# I2C_CAN.net
KiCad netlist of a schematic drawn in EAGLE
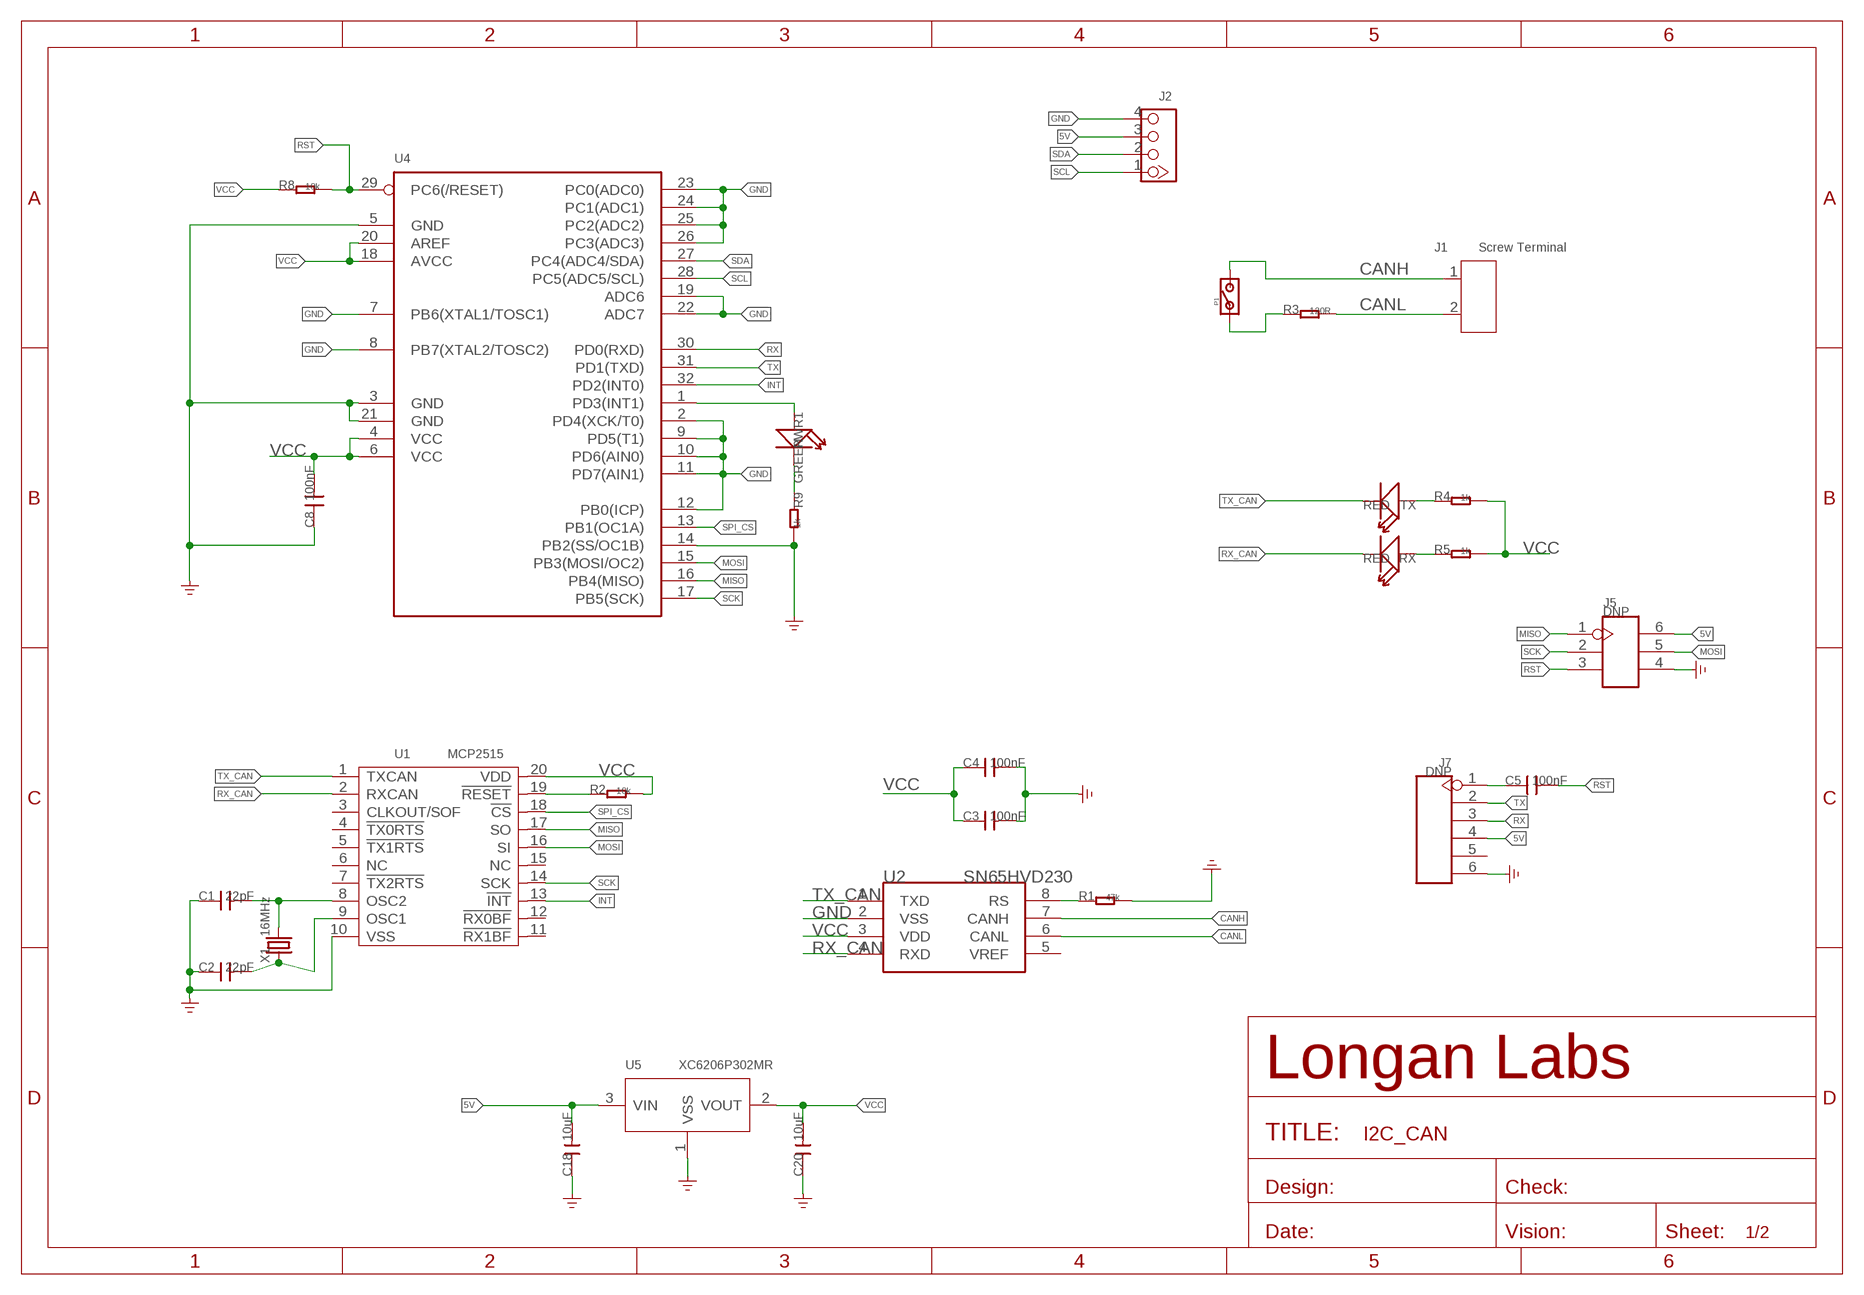
[diagram p0: schematic, sheet 1]

(export (version "E")
  (design (tool "Eeschema 10.0.6"))
  (components
    (comp (ref "C1")
      (value "22pF")
      (footprint "eagle-import:0603")
      (libsource (lib "eagle-import") (part "C-0603"))
    )
    (comp (ref "C2")
      (value "22pF")
      (footprint "eagle-import:0603")
      (libsource (lib "eagle-import") (part "C-0603"))
    )
    (comp (ref "C3")
      (value "100nF")
      (footprint "eagle-import:0603")
      (libsource (lib "eagle-import") (part "C-0603"))
    )
    (comp (ref "C4")
      (value "100nF")
      (footprint "eagle-import:0603")
      (libsource (lib "eagle-import") (part "C-0603"))
    )
    (comp (ref "C5")
      (value "100nF")
      (footprint "eagle-import:0603")
      (libsource (lib "eagle-import") (part "C-0603"))
    )
    (comp (ref "C8")
      (value "100nF")
      (footprint "eagle-import:0603")
      (libsource (lib "eagle-import") (part "C-0603"))
    )
    (comp (ref "C18")
      (value "10uF")
      (footprint "eagle-import:C0603")
      (libsource (lib "eagle-import") (part "CAP-0603"))
    )
    (comp (ref "C20")
      (value "10uF")
      (footprint "eagle-import:C0603")
      (libsource (lib "eagle-import") (part "CAP-0603"))
    )
    (comp (ref "J1")
      (value "Screw Terminal")
      (footprint "eagle-import:2P-3.5")
      (libsource (lib "eagle-import") (part "SCREW-TERMINAL-2P'3.5'"))
    )
    (comp (ref "J2")
      (value "320110033")
      (footprint "eagle-import:HW4-2.0")
      (libsource (lib "eagle-import") (part "GROVE-CONNECTOR-DIP-2.0"))
    )
    (comp (ref "J5")
      (value "DNP")
      (footprint "eagle-import:H2X3-SMD-2.0(1.143)")
      (libsource (lib "eagle-import") (part "HEADER-2X3P-2.0-1.143"))
    )
    (comp (ref "J7")
      (value "DNP")
      (footprint "eagle-import:H6-2.54")
      (libsource (lib "eagle-import") (part "HEADER-6P-55/35MIL"))
    )
    (comp (ref "P1")
      (value "PAD-JUMPER-2P")
      (footprint "eagle-import:2P-SMD-1.78X1.27")
      (libsource (lib "eagle-import") (part "PAD-JUMPER-2P"))
    )
    (comp (ref "PWR1")
      (value "GREEN")
      (footprint "eagle-import:LED-0603")
      (libsource (lib "eagle-import") (part "LED'0603'"))
    )
    (comp (ref "R1")
      (value "47k")
      (footprint "eagle-import:0603")
      (libsource (lib "eagle-import") (part "R-0603"))
    )
    (comp (ref "R2")
      (value "10k")
      (footprint "eagle-import:0603")
      (libsource (lib "eagle-import") (part "R-0603"))
    )
    (comp (ref "R3")
      (value "120R")
      (footprint "eagle-import:0603")
      (libsource (lib "eagle-import") (part "R-0603"))
    )
    (comp (ref "R4")
      (value "1k")
      (footprint "eagle-import:0603")
      (libsource (lib "eagle-import") (part "R-0603"))
    )
    (comp (ref "R5")
      (value "1k")
      (footprint "eagle-import:0603")
      (libsource (lib "eagle-import") (part "R-0603"))
    )
    (comp (ref "R8")
      (value "10k")
      (footprint "eagle-import:0603")
      (libsource (lib "eagle-import") (part "R-0603"))
    )
    (comp (ref "R9")
      (value "1k")
      (footprint "eagle-import:0603")
      (libsource (lib "eagle-import") (part "R-0603"))
    )
    (comp (ref "RX")
      (value "RED")
      (footprint "eagle-import:LED-0603")
      (libsource (lib "eagle-import") (part "LED'0603'"))
    )
    (comp (ref "TX")
      (value "RED")
      (footprint "eagle-import:LED-0603")
      (libsource (lib "eagle-import") (part "LED'0603'"))
    )
    (comp (ref "U1")
      (value "MCP2515")
      (footprint "eagle-import:TSSOP20-0.65-6.5X4.4MM")
      (libsource (lib "eagle-import") (part "MCP2515'ST'"))
    )
    (comp (ref "U2")
      (value "SN65HVD230")
      (footprint "eagle-import:SOIC8-6.0")
      (libsource (lib "eagle-import") (part "MCP2551-SOIC8"))
    )
    (comp (ref "U4")
      (value "MCU-ATMEGA8/168/328'AU'")
      (footprint "eagle-import:TQFP32-0.8-7X7MM")
      (libsource (lib "eagle-import") (part "MCU-ATMEGA8/168/328'AU'"))
    )
    (comp (ref "U5")
      (value "XC6206P302MR")
      (footprint "eagle-import:SOT-23")
      (libsource (lib "eagle-import") (part "PMIC-XC6206PMR"))
    )
    (comp (ref "X1")
      (value "16MHz")
      (footprint "eagle-import:HC49US")
      (libsource (lib "eagle-import") (part "CRYSTAL-2P'HC49US'"))
    )
  )
  (nets
    (net (code "1") (name "5V") (class "Default")
      (node (ref "C18") (pin "2") (pinfunction "2_2") (pintype "passive"))
      (node (ref "J2") (pin "3") (pinfunction "3_3") (pintype "bidirectional"))
      (node (ref "J5") (pin "6") (pinfunction "6_6") (pintype "bidirectional"))
      (node (ref "J7") (pin "4") (pinfunction "4_4") (pintype "bidirectional"))
      (node (ref "U5") (pin "3") (pinfunction "VIN_3") (pintype "bidirectional"))
    )
    (net (code "2") (name "CANH") (class "Default")
      (node (ref "J1") (pin "1") (pinfunction "1_1") (pintype "bidirectional"))
      (node (ref "P1") (pin "2") (pinfunction "2_2") (pintype "bidirectional"))
      (node (ref "U2") (pin "7") (pinfunction "CANH_7") (pintype "bidirectional"))
    )
    (net (code "3") (name "CANL") (class "Default")
      (node (ref "J1") (pin "2") (pinfunction "2_2") (pintype "bidirectional"))
      (node (ref "R3") (pin "2") (pinfunction "2_2") (pintype "passive"))
      (node (ref "U2") (pin "6") (pinfunction "CANL_6") (pintype "bidirectional"))
    )
    (net (code "4") (name "GND") (class "Default")
      (node (ref "C1") (pin "1") (pinfunction "1_1") (pintype "passive"))
      (node (ref "C18") (pin "1") (pinfunction "1_1") (pintype "passive"))
      (node (ref "C2") (pin "1") (pinfunction "1_1") (pintype "passive"))
      (node (ref "C20") (pin "1") (pinfunction "1_1") (pintype "passive"))
      (node (ref "C3") (pin "2") (pinfunction "2_2") (pintype "passive"))
      (node (ref "C4") (pin "2") (pinfunction "2_2") (pintype "passive"))
      (node (ref "C8") (pin "1") (pinfunction "1_1") (pintype "passive"))
      (node (ref "J2") (pin "4") (pinfunction "4_4") (pintype "bidirectional"))
      (node (ref "J5") (pin "4") (pinfunction "4_4") (pintype "bidirectional"))
      (node (ref "J7") (pin "6") (pinfunction "6_6") (pintype "bidirectional"))
      (node (ref "R1") (pin "2") (pinfunction "2_2") (pintype "passive"))
      (node (ref "R9") (pin "2") (pinfunction "2_2") (pintype "passive"))
      (node (ref "U1") (pin "10") (pinfunction "VSS_10") (pintype "bidirectional"))
      (node (ref "U2") (pin "2") (pinfunction "VSS_2") (pintype "bidirectional"))
      (node (ref "U4") (pin "10") (pinfunction "PD6(AIN0)_10") (pintype "bidirectional"))
      (node (ref "U4") (pin "11") (pinfunction "PD7(AIN1)_11") (pintype "bidirectional"))
      (node (ref "U4") (pin "12") (pinfunction "PB0(ICP)_12") (pintype "bidirectional"))
      (node (ref "U4") (pin "14") (pinfunction "PB2(SS/OC1B)_14") (pintype "bidirectional"))
      (node (ref "U4") (pin "19") (pinfunction "ADC6_19") (pintype "bidirectional"))
      (node (ref "U4") (pin "2") (pinfunction "PD4(XCK/T0)_2") (pintype "bidirectional"))
      (node (ref "U4") (pin "21") (pinfunction "GND_21") (pintype "bidirectional"))
      (node (ref "U4") (pin "22") (pinfunction "ADC7_22") (pintype "bidirectional"))
      (node (ref "U4") (pin "23") (pinfunction "PC0(ADC0)_23") (pintype "bidirectional"))
      (node (ref "U4") (pin "24") (pinfunction "PC1(ADC1)_24") (pintype "bidirectional"))
      (node (ref "U4") (pin "25") (pinfunction "PC2(ADC2)_25") (pintype "bidirectional"))
      (node (ref "U4") (pin "26") (pinfunction "PC3(ADC3)_26") (pintype "bidirectional"))
      (node (ref "U4") (pin "3") (pinfunction "GND_3") (pintype "bidirectional"))
      (node (ref "U4") (pin "5") (pinfunction "GND_5") (pintype "bidirectional"))
      (node (ref "U4") (pin "7") (pinfunction "PB6(XTAL1/TOSC1)_7") (pintype "bidirectional"))
      (node (ref "U4") (pin "8") (pinfunction "PB7(XTAL2/TOSC2)_8") (pintype "bidirectional"))
      (node (ref "U4") (pin "9") (pinfunction "PD5(T1)_9") (pintype "bidirectional"))
      (node (ref "U5") (pin "1") (pinfunction "VSS_1") (pintype "bidirectional"))
    )
    (net (code "5") (name "INT") (class "Default")
      (node (ref "U1") (pin "13") (pinfunction "~{INT}_13") (pintype "bidirectional"))
      (node (ref "U4") (pin "32") (pinfunction "PD2(INT0)_32") (pintype "bidirectional"))
    )
    (net (code "6") (name "MISO") (class "Default")
      (node (ref "J5") (pin "1") (pinfunction "1_1") (pintype "bidirectional"))
      (node (ref "U1") (pin "17") (pinfunction "SO_17") (pintype "bidirectional"))
      (node (ref "U4") (pin "16") (pinfunction "PB4(MISO)_16") (pintype "bidirectional"))
    )
    (net (code "7") (name "MOSI") (class "Default")
      (node (ref "J5") (pin "5") (pinfunction "5_5") (pintype "bidirectional"))
      (node (ref "U1") (pin "16") (pinfunction "SI_16") (pintype "bidirectional"))
      (node (ref "U4") (pin "15") (pinfunction "PB3(MOSI/OC2)_15") (pintype "bidirectional"))
    )
    (net (code "8") (name "Net-(C5-Pad1)") (class "Default")
      (node (ref "C5") (pin "1") (pinfunction "1_1") (pintype "passive"))
      (node (ref "J7") (pin "1") (pinfunction "1_1") (pintype "bidirectional"))
    )
    (net (code "9") (name "Net-(P1-Pad1)") (class "Default")
      (node (ref "P1") (pin "1") (pinfunction "1_1") (pintype "bidirectional"))
      (node (ref "R3") (pin "1") (pinfunction "1_1") (pintype "passive"))
    )
    (net (code "10") (name "Net-(PWR1-Pad-)") (class "Default")
      (node (ref "PWR1") (pin "-") (pinfunction "-_-") (pintype "passive"))
      (node (ref "R9") (pin "1") (pinfunction "1_1") (pintype "passive"))
    )
    (net (code "11") (name "Net-(R4-Pad1)") (class "Default")
      (node (ref "R4") (pin "1") (pinfunction "1_1") (pintype "passive"))
      (node (ref "TX") (pin "+") (pinfunction "+_+") (pintype "passive"))
    )
    (net (code "12") (name "Net-(R5-Pad1)") (class "Default")
      (node (ref "R5") (pin "1") (pinfunction "1_1") (pintype "passive"))
      (node (ref "RX") (pin "+") (pinfunction "+_+") (pintype "passive"))
    )
    (net (code "13") (name "Net-(U1-OSC1)") (class "Default")
      (node (ref "C2") (pin "2") (pinfunction "2_2") (pintype "passive"))
      (node (ref "U1") (pin "9") (pinfunction "OSC1_9") (pintype "bidirectional"))
      (node (ref "X1") (pin "1") (pinfunction "1_1") (pintype "passive"))
    )
    (net (code "14") (name "Net-(U1-OSC2)") (class "Default")
      (node (ref "C1") (pin "2") (pinfunction "2_2") (pintype "passive"))
      (node (ref "U1") (pin "8") (pinfunction "OSC2_8") (pintype "bidirectional"))
      (node (ref "X1") (pin "2") (pinfunction "2_2") (pintype "passive"))
    )
    (net (code "15") (name "Net-(U1-~{RESET})") (class "Default")
      (node (ref "R2") (pin "1") (pinfunction "1_1") (pintype "passive"))
      (node (ref "U1") (pin "19") (pinfunction "~{RESET}_19") (pintype "bidirectional"))
    )
    (net (code "16") (name "Net-(U2-RS)") (class "Default")
      (node (ref "R1") (pin "1") (pinfunction "1_1") (pintype "passive"))
      (node (ref "U2") (pin "8") (pinfunction "RS_8") (pintype "bidirectional"))
    )
    (net (code "17") (name "Net-(U4-PD3(INT1))") (class "Default")
      (node (ref "PWR1") (pin "+") (pinfunction "+_+") (pintype "passive"))
      (node (ref "U4") (pin "1") (pinfunction "PD3(INT1)_1") (pintype "bidirectional"))
    )
    (net (code "18") (name "RST") (class "Default")
      (node (ref "C5") (pin "2") (pinfunction "2_2") (pintype "passive"))
      (node (ref "J5") (pin "3") (pinfunction "3_3") (pintype "bidirectional"))
      (node (ref "R8") (pin "2") (pinfunction "2_2") (pintype "passive"))
      (node (ref "U4") (pin "29") (pinfunction "PC6(/RESET)_29") (pintype "bidirectional"))
    )
    (net (code "19") (name "RX") (class "Default")
      (node (ref "J7") (pin "3") (pinfunction "3_3") (pintype "bidirectional"))
      (node (ref "U4") (pin "30") (pinfunction "PD0(RXD)_30") (pintype "bidirectional"))
    )
    (net (code "20") (name "RX_CAN") (class "Default")
      (node (ref "RX") (pin "-") (pinfunction "-_-") (pintype "passive"))
      (node (ref "U1") (pin "2") (pinfunction "RXCAN_2") (pintype "bidirectional"))
      (node (ref "U2") (pin "4") (pinfunction "RXD_4") (pintype "bidirectional"))
    )
    (net (code "21") (name "SCK") (class "Default")
      (node (ref "J5") (pin "2") (pinfunction "2_2") (pintype "bidirectional"))
      (node (ref "U1") (pin "14") (pinfunction "SCK_14") (pintype "bidirectional"))
      (node (ref "U4") (pin "17") (pinfunction "PB5(SCK)_17") (pintype "bidirectional"))
    )
    (net (code "22") (name "SCL") (class "Default")
      (node (ref "J2") (pin "1") (pinfunction "1_1") (pintype "bidirectional"))
      (node (ref "U4") (pin "28") (pinfunction "PC5(ADC5/SCL)_28") (pintype "bidirectional"))
    )
    (net (code "23") (name "SDA") (class "Default")
      (node (ref "J2") (pin "2") (pinfunction "2_2") (pintype "bidirectional"))
      (node (ref "U4") (pin "27") (pinfunction "PC4(ADC4/SDA)_27") (pintype "bidirectional"))
    )
    (net (code "24") (name "SPI_CS") (class "Default")
      (node (ref "U1") (pin "18") (pinfunction "~{CS}_18") (pintype "bidirectional"))
      (node (ref "U4") (pin "13") (pinfunction "PB1(OC1A)_13") (pintype "bidirectional"))
    )
    (net (code "25") (name "TX") (class "Default")
      (node (ref "J7") (pin "2") (pinfunction "2_2") (pintype "bidirectional"))
      (node (ref "U4") (pin "31") (pinfunction "PD1(TXD)_31") (pintype "bidirectional"))
    )
    (net (code "26") (name "TX_CAN") (class "Default")
      (node (ref "TX") (pin "-") (pinfunction "-_-") (pintype "passive"))
      (node (ref "U1") (pin "1") (pinfunction "TXCAN_1") (pintype "bidirectional"))
      (node (ref "U2") (pin "1") (pinfunction "TXD_1") (pintype "bidirectional"))
    )
    (net (code "27") (name "VCC") (class "Default")
      (node (ref "C20") (pin "2") (pinfunction "2_2") (pintype "passive"))
      (node (ref "C3") (pin "1") (pinfunction "1_1") (pintype "passive"))
      (node (ref "C4") (pin "1") (pinfunction "1_1") (pintype "passive"))
      (node (ref "C8") (pin "2") (pinfunction "2_2") (pintype "passive"))
      (node (ref "R2") (pin "2") (pinfunction "2_2") (pintype "passive"))
      (node (ref "R4") (pin "2") (pinfunction "2_2") (pintype "passive"))
      (node (ref "R5") (pin "2") (pinfunction "2_2") (pintype "passive"))
      (node (ref "R8") (pin "1") (pinfunction "1_1") (pintype "passive"))
      (node (ref "U1") (pin "20") (pinfunction "VDD_20") (pintype "bidirectional"))
      (node (ref "U2") (pin "3") (pinfunction "VDD_3") (pintype "bidirectional"))
      (node (ref "U4") (pin "18") (pinfunction "AVCC_18") (pintype "bidirectional"))
      (node (ref "U4") (pin "20") (pinfunction "AREF_20") (pintype "bidirectional"))
      (node (ref "U4") (pin "4") (pinfunction "VCC_4") (pintype "bidirectional"))
      (node (ref "U4") (pin "6") (pinfunction "VCC_6") (pintype "bidirectional"))
      (node (ref "U5") (pin "2") (pinfunction "VOUT_2") (pintype "bidirectional"))
    )
    (net (code "28") (name "unconnected-(J7-Pad5)") (class "Default")
      (node (ref "J7") (pin "5") (pinfunction "5_5") (pintype "bidirectional"))
    )
    (net (code "29") (name "unconnected-(U1-CLKOUT{slash}SOF-Pad3)") (class "Default")
      (node (ref "U1") (pin "3") (pinfunction "CLKOUT/SOF_3") (pintype "bidirectional"))
    )
    (net (code "30") (name "unconnected-(U1-NC-Pad6)") (class "Default")
      (node (ref "U1") (pin "6") (pinfunction "NC_6") (pintype "bidirectional"))
    )
    (net (code "31") (name "unconnected-(U1-NC-Pad15)") (class "Default")
      (node (ref "U1") (pin "15") (pinfunction "NC_15") (pintype "bidirectional"))
    )
    (net (code "32") (name "unconnected-(U1-~{RX0BF}-Pad12)") (class "Default")
      (node (ref "U1") (pin "12") (pinfunction "~{RX0BF}_12") (pintype "bidirectional"))
    )
    (net (code "33") (name "unconnected-(U1-~{RX1BF}-Pad11)") (class "Default")
      (node (ref "U1") (pin "11") (pinfunction "~{RX1BF}_11") (pintype "bidirectional"))
    )
    (net (code "34") (name "unconnected-(U1-~{TX0RTS}-Pad4)") (class "Default")
      (node (ref "U1") (pin "4") (pinfunction "~{TX0RTS}_4") (pintype "bidirectional"))
    )
    (net (code "35") (name "unconnected-(U1-~{TX1RTS}-Pad5)") (class "Default")
      (node (ref "U1") (pin "5") (pinfunction "~{TX1RTS}_5") (pintype "bidirectional"))
    )
    (net (code "36") (name "unconnected-(U1-~{TX2RTS}-Pad7)") (class "Default")
      (node (ref "U1") (pin "7") (pinfunction "~{TX2RTS}_7") (pintype "bidirectional"))
    )
    (net (code "37") (name "unconnected-(U2-VREF-Pad5)") (class "Default")
      (node (ref "U2") (pin "5") (pinfunction "VREF_5") (pintype "bidirectional"))
    )
  )
)
